# 01_POWER.net
KiCad netlist of a schematic drawn in Altium Designer
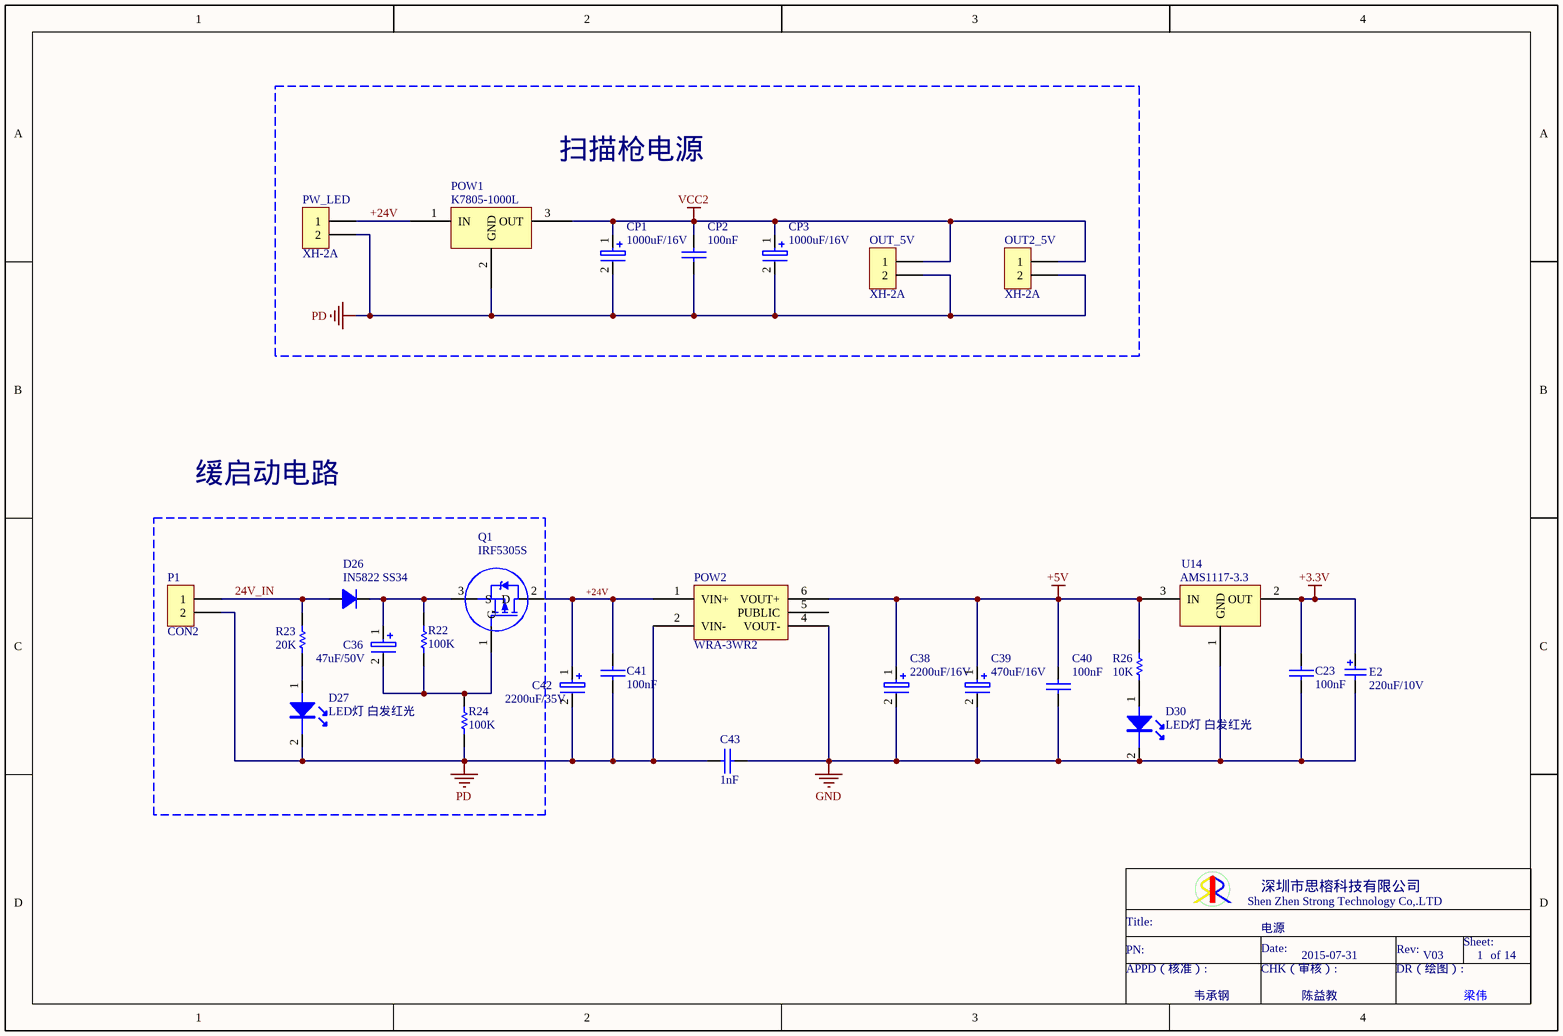
[diagram p0: 01_POWER.SchDoc]

(export (version "E")
  (design (tool "Eeschema 10.0.6"))
  (components
    (comp (ref "C23") (value "100nF") (footprint "0603C") (libsource (lib "WeiCHGSCH") (part "CAP")))
    (comp (ref "C36")
      (value "47uF/50V")
      (footprint "RB6.3*11")
      (description "电解电容器")
      (libsource (lib "Mylibrary") (part "CAP2"))
    )
    (comp (ref "C38")
      (value "2200uF/16V")
      (footprint "RB10*20")
      (description "电解电容器")
      (libsource (lib "Mylibrary") (part "CAP2"))
    )
    (comp (ref "C39")
      (value "470uF/16V")
      (footprint "RB8*11.5")
      (description "电解电容器")
      (libsource (lib "Mylibrary") (part "CAP2"))
    )
    (comp (ref "C40")
      (value "100nF")
      (footprint "0805C")
      (description "Capacitor")
      (libsource (lib "*") (part "CAP"))
    )
    (comp (ref "C41")
      (value "100nF")
      (footprint "0805C")
      (description "Capacitor")
      (libsource (lib "*") (part "CAP"))
    )
    (comp (ref "C42")
      (value "2200uF/35V")
      (footprint "RB16*25")
      (description "电解电容器")
      (libsource (lib "Mylibrary") (part "CAP2"))
    )
    (comp (ref "C43")
      (value "1nF")
      (footprint "1206C")
      (description "Capacitor")
      (libsource (lib "*") (part "CAP"))
    )
    (comp (ref "CP1")
      (value "1000uF/16V")
      (footprint "RB8*11.5")
      (description "电解电容器")
      (libsource (lib "Mylibrary") (part "CAP2"))
    )
    (comp (ref "CP2")
      (value "100nF")
      (footprint "0805C")
      (description "Capacitor")
      (libsource (lib "*") (part "CAP"))
    )
    (comp (ref "CP3")
      (value "1000uF/16V")
      (footprint "RB8*11.5")
      (description "电解电容器")
      (libsource (lib "Mylibrary") (part "CAP2"))
    )
    (comp (ref "D26") (value "IN5822 SS34") (footprint "DO-214AA") (libsource (lib "*") (part "DIODE-D")))
    (comp (ref "D27")
      (value "LED灯 白发红光")
      (footprint "D0603")
      (description "LED灯")
      (libsource (lib "Mylibrary") (part "LED"))
    )
    (comp (ref "D30")
      (value "LED灯 白发红光")
      (footprint "D0603")
      (description "LED灯")
      (libsource (lib "Mylibrary") (part "LED"))
    )
    (comp (ref "E2")
      (value "220uF/10V")
      (footprint "6032")
      (description "Bi-Polar Capacitor")
      (libsource (lib "*") (part "电解电容"))
    )
    (comp (ref "OUT2_5V") (value "XH-2A") (footprint "CN2-2.54") (libsource (lib "WeiCHGSCH") (part "CON2")))
    (comp (ref "OUT_5V") (value "XH-2A") (footprint "CN2-2.54") (libsource (lib "WeiCHGSCH") (part "CON2")))
    (comp (ref "P1") (value "CON2") (footprint "CON-2_5.08") (libsource (lib "WeiCHGSCH") (part "CON2")))
    (comp (ref "POW1")
      (value "K7805-1000L")
      (footprint "K7805-1000L")
      (libsource (lib "Mylibrary") (part "K7805-1000L"))
    )
    (comp (ref "POW2")
      (value "WRA-3WR2")
      (footprint "WRA-3WR2")
      (libsource (lib "Schlib1") (part "Component_1"))
    )
    (comp (ref "PW_LED") (value "XH-2A") (footprint "CN2-2.54") (libsource (lib "WeiCHGSCH") (part "CON2")))
    (comp (ref "Q1")
      (value "IRF5305S")
      (footprint "TO-252")
      (description "P型MOSFET")
      (libsource (lib "LGA") (part "MOSFET-P"))
    )
    (comp (ref "R22") (value "100K") (footprint "0805R") (libsource (lib "Mylibrary") (part "RES")))
    (comp (ref "R23") (value "20K") (footprint "0805R") (libsource (lib "Mylibrary") (part "RES")))
    (comp (ref "R24") (value "100K") (footprint "0805R") (libsource (lib "Mylibrary") (part "RES")))
    (comp (ref "R26") (value "10K") (footprint "0603R") (libsource (lib "Mylibrary") (part "RES")))
    (comp (ref "U14") (value "AMS1117-3.3") (footprint "SOT223_CX1117") (libsource (lib "*") (part "CX1117")))
  )
  (nets
    (net (code "1") (name "+3.3V") (class "Default")
      (node (ref "C23") (pin "2") (pinfunction "2_2") (pintype "passive"))
      (node (ref "E2") (pin "1") (pinfunction "1_1") (pintype "passive"))
      (node (ref "U14") (pin "2") (pinfunction "OUT_2") (pintype "passive"))
    )
    (net (code "2") (name "+5V") (class "Default")
      (node (ref "C38") (pin "1") (pinfunction "1_1") (pintype "passive"))
      (node (ref "C39") (pin "1") (pinfunction "1_1") (pintype "passive"))
      (node (ref "C40") (pin "1") (pinfunction "1_1") (pintype "passive"))
      (node (ref "POW2") (pin "6") (pinfunction "VOUT+_6") (pintype "passive"))
      (node (ref "R26") (pin "2") (pinfunction "2_2") (pintype "passive"))
      (node (ref "U14") (pin "3") (pinfunction "IN_3") (pintype "passive"))
    )
    (net (code "3") (name "/+24V") (class "Default")
      (node (ref "C41") (pin "1") (pinfunction "1_1") (pintype "passive"))
      (node (ref "C42") (pin "1") (pinfunction "1_1") (pintype "passive"))
      (node (ref "POW1") (pin "1") (pinfunction "IN_1") (pintype "passive"))
      (node (ref "POW2") (pin "1") (pinfunction "VIN+_1") (pintype "passive"))
      (node (ref "PW_LED") (pin "1") (pinfunction "1_1") (pintype "passive"))
      (node (ref "Q1") (pin "2") (pinfunction "D_2") (pintype "passive"))
    )
    (net (code "4") (name "/24V_IN") (class "Default")
      (node (ref "D26") (pin "1") (pinfunction "1_1") (pintype "passive"))
      (node (ref "P1") (pin "1") (pinfunction "1_1") (pintype "passive"))
      (node (ref "R23") (pin "2") (pinfunction "2_2") (pintype "passive"))
    )
    (net (code "5") (name "GND") (class "Default")
      (node (ref "C23") (pin "1") (pinfunction "1_1") (pintype "passive"))
      (node (ref "C38") (pin "2") (pinfunction "2_2") (pintype "passive"))
      (node (ref "C39") (pin "2") (pinfunction "2_2") (pintype "passive"))
      (node (ref "C40") (pin "2") (pinfunction "2_2") (pintype "passive"))
      (node (ref "C43") (pin "2") (pinfunction "2_2") (pintype "passive"))
      (node (ref "D30") (pin "2") (pinfunction "2_2") (pintype "passive"))
      (node (ref "E2") (pin "2") (pinfunction "2_2") (pintype "passive"))
      (node (ref "POW2") (pin "4") (pinfunction "VOUT-_4") (pintype "passive"))
      (node (ref "U14") (pin "1") (pinfunction "GND_1") (pintype "passive"))
    )
    (net (code "6") (name "Net-(D27-Pad1)") (class "Default")
      (node (ref "D27") (pin "1") (pinfunction "1_1") (pintype "passive"))
      (node (ref "R23") (pin "1") (pinfunction "1_1") (pintype "passive"))
    )
    (net (code "7") (name "Net-(D30-Pad1)") (class "Default")
      (node (ref "D30") (pin "1") (pinfunction "1_1") (pintype "passive"))
      (node (ref "R26") (pin "1") (pinfunction "1_1") (pintype "passive"))
    )
    (net (code "8") (name "Net-(Q1-G)") (class "Default")
      (node (ref "C36") (pin "2") (pinfunction "2_2") (pintype "passive"))
      (node (ref "Q1") (pin "1") (pinfunction "G_1") (pintype "passive"))
      (node (ref "R22") (pin "1") (pinfunction "1_1") (pintype "passive"))
      (node (ref "R24") (pin "2") (pinfunction "2_2") (pintype "passive"))
    )
    (net (code "9") (name "Net-(Q1-S)") (class "Default")
      (node (ref "C36") (pin "1") (pinfunction "1_1") (pintype "passive"))
      (node (ref "D26") (pin "2") (pinfunction "2_2") (pintype "passive"))
      (node (ref "Q1") (pin "3") (pinfunction "S_3") (pintype "passive"))
      (node (ref "R22") (pin "2") (pinfunction "2_2") (pintype "passive"))
    )
    (net (code "10") (name "PD") (class "Default")
      (node (ref "C41") (pin "2") (pinfunction "2_2") (pintype "passive"))
      (node (ref "C42") (pin "2") (pinfunction "2_2") (pintype "passive"))
      (node (ref "C43") (pin "1") (pinfunction "1_1") (pintype "passive"))
      (node (ref "CP1") (pin "2") (pinfunction "2_2") (pintype "passive"))
      (node (ref "CP2") (pin "2") (pinfunction "2_2") (pintype "passive"))
      (node (ref "CP3") (pin "2") (pinfunction "2_2") (pintype "passive"))
      (node (ref "D27") (pin "2") (pinfunction "2_2") (pintype "passive"))
      (node (ref "OUT2_5V") (pin "2") (pinfunction "2_2") (pintype "passive"))
      (node (ref "OUT_5V") (pin "2") (pinfunction "2_2") (pintype "passive"))
      (node (ref "P1") (pin "2") (pinfunction "2_2") (pintype "passive"))
      (node (ref "POW1") (pin "2") (pinfunction "GND_2") (pintype "passive"))
      (node (ref "POW2") (pin "2") (pinfunction "VIN-_2") (pintype "passive"))
      (node (ref "PW_LED") (pin "2") (pinfunction "2_2") (pintype "passive"))
      (node (ref "R24") (pin "1") (pinfunction "1_1") (pintype "passive"))
    )
    (net (code "11") (name "VCC2") (class "Default")
      (node (ref "CP1") (pin "1") (pinfunction "1_1") (pintype "passive"))
      (node (ref "CP2") (pin "1") (pinfunction "1_1") (pintype "passive"))
      (node (ref "CP3") (pin "1") (pinfunction "1_1") (pintype "passive"))
      (node (ref "OUT2_5V") (pin "1") (pinfunction "1_1") (pintype "passive"))
      (node (ref "OUT_5V") (pin "1") (pinfunction "1_1") (pintype "passive"))
      (node (ref "POW1") (pin "3") (pinfunction "OUT_3") (pintype "passive"))
    )
    (net (code "12") (name "unconnected-(POW2-PUBLIC-Pad5)") (class "Default")
      (node (ref "POW2") (pin "5") (pinfunction "PUBLIC_5") (pintype "passive"))
    )
  )
)
